# System_Ports.net
KiCad netlist of a schematic drawn in Altium Designer
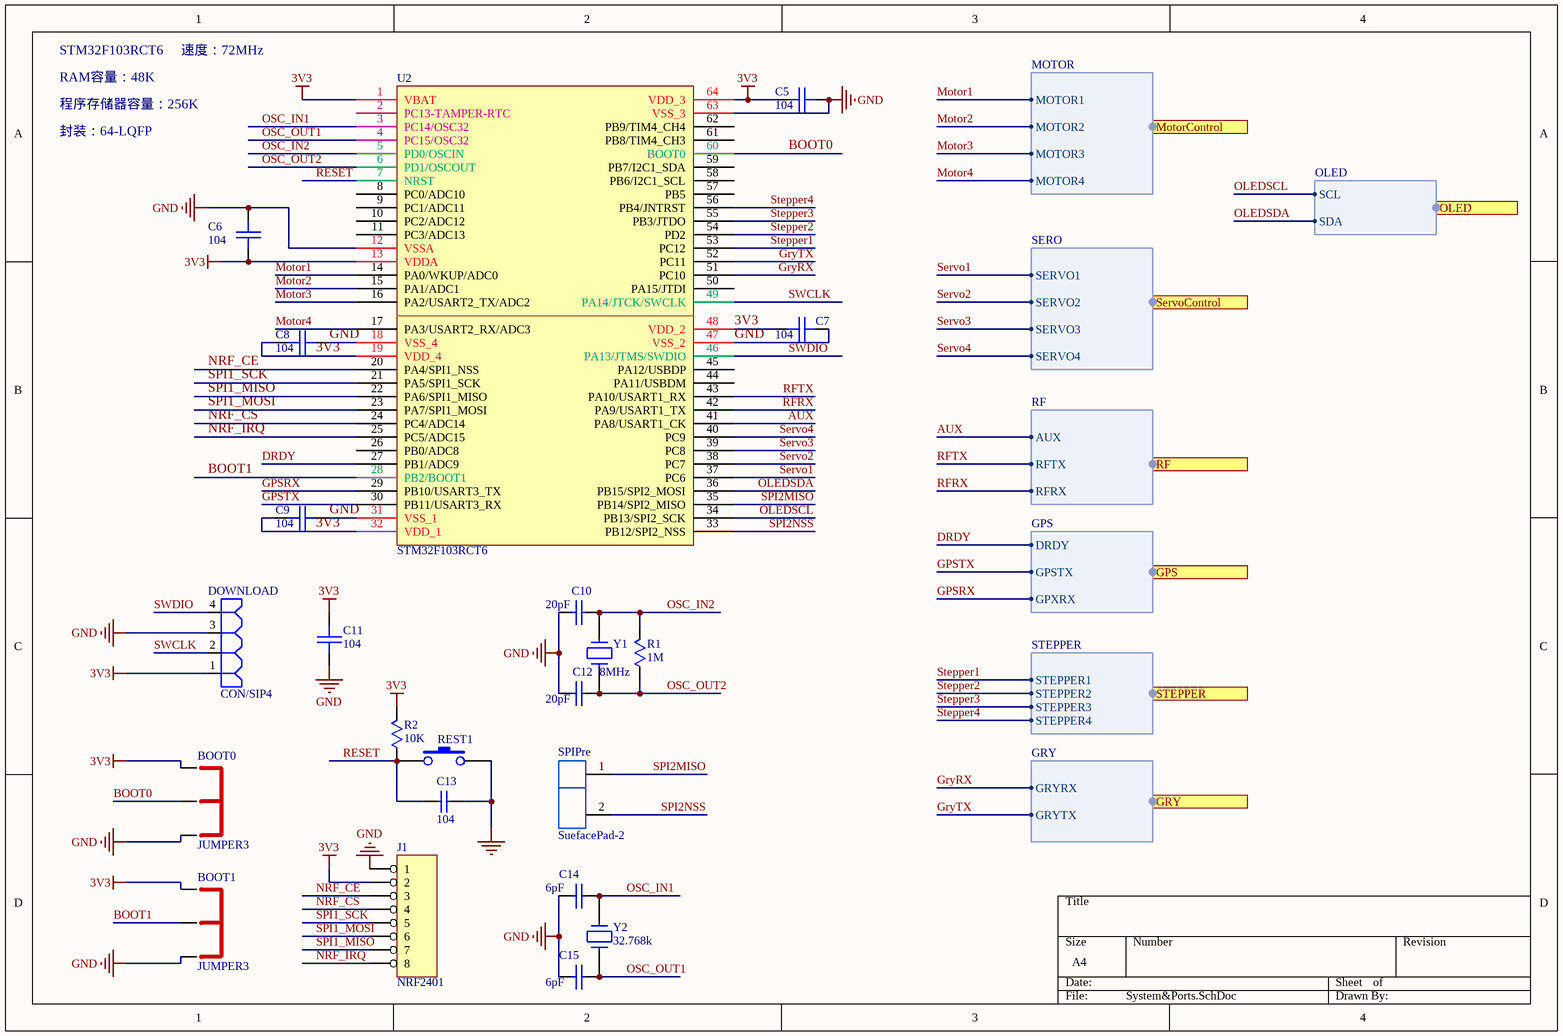
[diagram p0: System&Ports.SchDoc]

(export (version "E")
  (design (tool "Eeschema 10.0.6"))
  (components
    (comp (ref "BOOT0")
      (value "JUMPER3")
      (footprint "Jumper3")
      (description "Jumper")
      (libsource (lib "LQ_Integrated_Library") (part "JUMPER3"))
    )
    (comp (ref "BOOT1")
      (value "JUMPER3")
      (footprint "Jumper3")
      (description "Jumper")
      (libsource (lib "LQ_Integrated_Library") (part "JUMPER3"))
    )
    (comp (ref "C5") (value "104") (footprint "C0603") (libsource (lib "YT1_SCH_99SE") (part "CAP")))
    (comp (ref "C6") (value "104") (footprint "C0603") (libsource (lib "YT1_SCH_99SE") (part "CAP")))
    (comp (ref "C7") (value "104") (footprint "C0603") (libsource (lib "YT1_SCH_99SE") (part "CAP")))
    (comp (ref "C8") (value "104") (footprint "C0603") (libsource (lib "YT1_SCH_99SE") (part "CAP")))
    (comp (ref "C9") (value "104") (footprint "C0603") (libsource (lib "YT1_SCH_99SE") (part "CAP")))
    (comp (ref "C10")
      (value "20pF")
      (footprint "LC-0603_C")
      (description "CAP CHIP 20P 50V(+-5% C0G 0603)")
      (libsource (lib "Miscellaneous Devices") (part "CAP"))
    )
    (comp (ref "C11") (value "104") (footprint "C0603") (libsource (lib "YT1_SCH_99SE") (part "CAP")))
    (comp (ref "C12")
      (value "20pF")
      (footprint "LC-0603_C")
      (description "CAP CHIP 20P 50V(+-5% C0G 0603)")
      (libsource (lib "Miscellaneous Devices") (part "CAP"))
    )
    (comp (ref "C13")
      (value "104")
      (footprint "LC-0603_C")
      (description "GRM39 X7R102K50PT")
      (fields (field (name "PUBLISHER") "Altium Limited"))
      (libsource (lib "") (part "CAP_1"))
    )
    (comp (ref "C14")
      (value "6pF")
      (footprint "LC-0603_C")
      (description "CAP CHIP 20P 50V(+-5% C0G 0603)")
      (libsource (lib "Miscellaneous Devices") (part "CAP"))
    )
    (comp (ref "C15")
      (value "6pF")
      (footprint "LC-0603_C")
      (description "CAP CHIP 20P 50V(+-5% C0G 0603)")
      (libsource (lib "Miscellaneous Devices") (part "CAP"))
    )
    (comp (ref "DOWNLOAD")
      (value "CON/SIP4")
      (footprint "HDR1X4")
      (libsource (lib "LQ_Integrated_Library") (part "CON/SIP4"))
    )
    (comp (ref "J1")
      (value "NRF2401")
      (footprint "HDR2X4")
      (description "8 Pin Header")
      (libsource (lib "YT1_SCH_99SE") (part "HEADER 8"))
    )
    (comp (ref "R1") (value "1M") (footprint "LC-0603_R") (libsource (lib "YT1_SCH_99SE") (part "RES")))
    (comp (ref "R2") (value "10K") (footprint "R0603") (libsource (lib "YT1_SCH_99SE") (part "RES")))
    (comp (ref "REST1") (value "~") (footprint "KEY-K2") (libsource (lib "*") (part "SW-PB")))
    (comp (ref "SPIPre")
      (value "SuefacePad-2")
      (footprint "SurfacePad-2")
      (libsource (lib "FlyAndDive") (part "SurfacePad-2"))
    )
    (comp (ref "U2")
      (value "STM32F103RCT6")
      (footprint "LC-LQFP-64_10x10x05P")
      (libsource (lib "YT1_SCH_99SE") (part "STM32F103RBT6"))
    )
    (comp (ref "Y1")
      (value "8MHz")
      (footprint "XTAL-49/S_N")
      (description "Crystal 8MHz PLUG")
      (libsource (lib "*") (part "CRYSTAL"))
    )
    (comp (ref "Y2")
      (value "32.768k")
      (footprint "XTAL_2X6 卧式")
      (description "Crystal 8MHz PLUG")
      (libsource (lib "*") (part "CRYSTAL"))
    )
  )
  (nets
    (net (code "8") (name "/AUX") (class "Default")
      (node (ref "U2") (pin "41") (pinfunction "PA8/USART1_CK_41") (pintype "passive"))
    )
    (net (code "9") (name "/BOOT0") (class "Default")
      (node (ref "BOOT0") (pin "2") (pinfunction "2_2") (pintype "passive"))
      (node (ref "U2") (pin "60") (pinfunction "BOOT0_60") (pintype "passive"))
    )
    (net (code "10") (name "/BOOT1") (class "Default")
      (node (ref "BOOT1") (pin "2") (pinfunction "2_2") (pintype "passive"))
      (node (ref "U2") (pin "28") (pinfunction "PB2/BOOT1_28") (pintype "passive"))
    )
    (net (code "11") (name "/DRDY") (class "Default")
      (node (ref "U2") (pin "27") (pinfunction "PB1/ADC9_27") (pintype "passive"))
    )
    (net (code "12") (name "/GPSRX") (class "Default")
      (node (ref "U2") (pin "29") (pinfunction "PB10/USART3_TX_29") (pintype "passive"))
    )
    (net (code "13") (name "/GPSTX") (class "Default")
      (node (ref "U2") (pin "30") (pinfunction "PB11/USART3_RX_30") (pintype "passive"))
    )
    (net (code "14") (name "/GryRX") (class "Default")
      (node (ref "U2") (pin "51") (pinfunction "PC10_51") (pintype "passive"))
    )
    (net (code "15") (name "/GryTX") (class "Default")
      (node (ref "U2") (pin "52") (pinfunction "PC11_52") (pintype "passive"))
    )
    (net (code "16") (name "/Motor1") (class "Default")
      (node (ref "U2") (pin "14") (pinfunction "PA0/WKUP/ADC0_14") (pintype "passive"))
    )
    (net (code "17") (name "/Motor2") (class "Default")
      (node (ref "U2") (pin "15") (pinfunction "PA1/ADC1_15") (pintype "passive"))
    )
    (net (code "18") (name "/Motor3") (class "Default")
      (node (ref "U2") (pin "16") (pinfunction "PA2/USART2_TX/ADC2_16") (pintype "passive"))
    )
    (net (code "19") (name "/Motor4") (class "Default")
      (node (ref "U2") (pin "17") (pinfunction "PA3/USART2_RX/ADC3_17") (pintype "passive"))
    )
    (net (code "20") (name "/NRF_CE") (class "Default")
      (node (ref "J1") (pin "3") (pinfunction "3_3") (pintype "passive"))
      (node (ref "U2") (pin "20") (pinfunction "PA4/SPI1_NSS_20") (pintype "passive"))
    )
    (net (code "21") (name "/NRF_CS") (class "Default")
      (node (ref "J1") (pin "4") (pinfunction "4_4") (pintype "passive"))
      (node (ref "U2") (pin "24") (pinfunction "PC4/ADC14_24") (pintype "passive"))
    )
    (net (code "22") (name "/NRF_IRQ") (class "Default")
      (node (ref "J1") (pin "8") (pinfunction "8_8") (pintype "passive"))
      (node (ref "U2") (pin "25") (pinfunction "PC5/ADC15_25") (pintype "passive"))
    )
    (net (code "23") (name "/OLEDSCL") (class "Default")
      (node (ref "U2") (pin "34") (pinfunction "PB13/SPI2_SCK_34") (pintype "passive"))
    )
    (net (code "24") (name "/OLEDSDA") (class "Default")
      (node (ref "U2") (pin "36") (pinfunction "PB15/SPI2_MOSI_36") (pintype "passive"))
    )
    (net (code "25") (name "/OSC_IN1") (class "Default")
      (node (ref "C14") (pin "2") (pinfunction "2_2") (pintype "passive"))
      (node (ref "U2") (pin "3") (pinfunction "PC14/OSC32_3") (pintype "passive"))
      (node (ref "Y2") (pin "2") (pinfunction "2_2") (pintype "passive"))
    )
    (net (code "26") (name "/OSC_IN2") (class "Default")
      (node (ref "C10") (pin "2") (pinfunction "2_2") (pintype "passive"))
      (node (ref "R1") (pin "2") (pinfunction "2_2") (pintype "passive"))
      (node (ref "U2") (pin "5") (pinfunction "PD0/OSCIN_5") (pintype "passive"))
      (node (ref "Y1") (pin "1") (pinfunction "1_1") (pintype "passive"))
    )
    (net (code "27") (name "/OSC_OUT1") (class "Default")
      (node (ref "C15") (pin "2") (pinfunction "2_2") (pintype "passive"))
      (node (ref "U2") (pin "4") (pinfunction "PC15/OSC32_4") (pintype "passive"))
      (node (ref "Y2") (pin "1") (pinfunction "1_1") (pintype "passive"))
    )
    (net (code "28") (name "/OSC_OUT2") (class "Default")
      (node (ref "C12") (pin "2") (pinfunction "2_2") (pintype "passive"))
      (node (ref "R1") (pin "1") (pinfunction "1_1") (pintype "passive"))
      (node (ref "U2") (pin "6") (pinfunction "PD1/OSCOUT_6") (pintype "passive"))
      (node (ref "Y1") (pin "2") (pinfunction "2_2") (pintype "passive"))
    )
    (net (code "29") (name "/RESET") (class "Default")
      (node (ref "C13") (pin "2") (pinfunction "2_2") (pintype "passive"))
      (node (ref "R2") (pin "1") (pinfunction "1_1") (pintype "passive"))
      (node (ref "REST1") (pin "1") (pinfunction "1_1") (pintype "passive"))
      (node (ref "U2") (pin "7") (pinfunction "NRST_7") (pintype "passive"))
    )
    (net (code "30") (name "/RFRX") (class "Default")
      (node (ref "U2") (pin "42") (pinfunction "PA9/USART1_TX_42") (pintype "passive"))
    )
    (net (code "31") (name "/RFTX") (class "Default")
      (node (ref "U2") (pin "43") (pinfunction "PA10/USART1_RX_43") (pintype "passive"))
    )
    (net (code "32") (name "/SPI1_MISO") (class "Default")
      (node (ref "J1") (pin "7") (pinfunction "7_7") (pintype "passive"))
      (node (ref "U2") (pin "22") (pinfunction "PA6/SPI1_MISO_22") (pintype "passive"))
    )
    (net (code "33") (name "/SPI1_MOSI") (class "Default")
      (node (ref "J1") (pin "6") (pinfunction "6_6") (pintype "passive"))
      (node (ref "U2") (pin "23") (pinfunction "PA7/SPI1_MOSI_23") (pintype "passive"))
    )
    (net (code "34") (name "/SPI1_SCK") (class "Default")
      (node (ref "J1") (pin "5") (pinfunction "5_5") (pintype "passive"))
      (node (ref "U2") (pin "21") (pinfunction "PA5/SPI1_SCK_21") (pintype "passive"))
    )
    (net (code "35") (name "/SPI2MISO") (class "Default")
      (node (ref "SPIPre") (pin "1") (pinfunction "1_1") (pintype "passive"))
      (node (ref "U2") (pin "35") (pinfunction "PB14/SPI2_MISO_35") (pintype "passive"))
    )
    (net (code "36") (name "/SPI2NSS") (class "Default")
      (node (ref "SPIPre") (pin "2") (pinfunction "2_2") (pintype "passive"))
      (node (ref "U2") (pin "33") (pinfunction "PB12/SPI2_NSS_33") (pintype "passive"))
    )
    (net (code "37") (name "/SWCLK") (class "Default")
      (node (ref "DOWNLOAD") (pin "2") (pintype "passive"))
      (node (ref "U2") (pin "49") (pinfunction "PA14/JTCK/SWCLK_49") (pintype "passive"))
    )
    (net (code "38") (name "/SWDIO") (class "Default")
      (node (ref "DOWNLOAD") (pin "4") (pintype "passive"))
      (node (ref "U2") (pin "46") (pinfunction "PA13/JTMS/SWDIO_46") (pintype "passive"))
    )
    (net (code "39") (name "/Servo1") (class "Default")
      (node (ref "U2") (pin "37") (pinfunction "PC6_37") (pintype "passive"))
    )
    (net (code "40") (name "/Servo2") (class "Default")
      (node (ref "U2") (pin "38") (pinfunction "PC7_38") (pintype "passive"))
    )
    (net (code "41") (name "/Servo3") (class "Default")
      (node (ref "U2") (pin "39") (pinfunction "PC8_39") (pintype "passive"))
    )
    (net (code "42") (name "/Servo4") (class "Default")
      (node (ref "U2") (pin "40") (pinfunction "PC9_40") (pintype "passive"))
    )
    (net (code "43") (name "/Stepper1") (class "Default")
      (node (ref "U2") (pin "53") (pinfunction "PC12_53") (pintype "passive"))
    )
    (net (code "44") (name "/Stepper2") (class "Default")
      (node (ref "U2") (pin "54") (pinfunction "PD2_54") (pintype "passive"))
    )
    (net (code "45") (name "/Stepper3") (class "Default")
      (node (ref "U2") (pin "55") (pinfunction "PB3/JTDO_55") (pintype "passive"))
    )
    (net (code "46") (name "/Stepper4") (class "Default")
      (node (ref "U2") (pin "56") (pinfunction "PB4/JNTRST_56") (pintype "passive"))
    )
    (net (code "54") (name "3V3") (class "Default")
      (node (ref "BOOT0") (pin "1") (pinfunction "1_1") (pintype "passive"))
      (node (ref "BOOT1") (pin "1") (pinfunction "1_1") (pintype "passive"))
      (node (ref "C11") (pin "1") (pinfunction "1_1") (pintype "passive"))
      (node (ref "C5") (pin "1") (pinfunction "1_1") (pintype "passive"))
      (node (ref "C6") (pin "2") (pinfunction "2_2") (pintype "passive"))
      (node (ref "C7") (pin "1") (pinfunction "1_1") (pintype "passive"))
      (node (ref "C8") (pin "1") (pinfunction "1_1") (pintype "passive"))
      (node (ref "C9") (pin "1") (pinfunction "1_1") (pintype "passive"))
      (node (ref "DOWNLOAD") (pin "1") (pintype "passive"))
      (node (ref "J1") (pin "2") (pinfunction "2_2") (pintype "passive"))
      (node (ref "R2") (pin "2") (pinfunction "2_2") (pintype "passive"))
      (node (ref "U2") (pin "1") (pinfunction "VBAT_1") (pintype "passive"))
      (node (ref "U2") (pin "13") (pinfunction "VDDA_13") (pintype "passive"))
      (node (ref "U2") (pin "19") (pinfunction "VDD_4_19") (pintype "passive"))
      (node (ref "U2") (pin "32") (pinfunction "VDD_1_32") (pintype "passive"))
      (node (ref "U2") (pin "48") (pinfunction "VDD_2_48") (pintype "passive"))
      (node (ref "U2") (pin "64") (pinfunction "VDD_3_64") (pintype "passive"))
    )
    (net (code "55") (name "GND") (class "Default")
      (node (ref "BOOT0") (pin "3") (pinfunction "3_3") (pintype "passive"))
      (node (ref "BOOT1") (pin "3") (pinfunction "3_3") (pintype "passive"))
      (node (ref "C10") (pin "1") (pinfunction "1_1") (pintype "passive"))
      (node (ref "C11") (pin "2") (pinfunction "2_2") (pintype "passive"))
      (node (ref "C12") (pin "1") (pinfunction "1_1") (pintype "passive"))
      (node (ref "C13") (pin "1") (pinfunction "1_1") (pintype "passive"))
      (node (ref "C14") (pin "1") (pinfunction "1_1") (pintype "passive"))
      (node (ref "C15") (pin "1") (pinfunction "1_1") (pintype "passive"))
      (node (ref "C5") (pin "2") (pinfunction "2_2") (pintype "passive"))
      (node (ref "C6") (pin "1") (pinfunction "1_1") (pintype "passive"))
      (node (ref "C7") (pin "2") (pinfunction "2_2") (pintype "passive"))
      (node (ref "C8") (pin "2") (pinfunction "2_2") (pintype "passive"))
      (node (ref "C9") (pin "2") (pinfunction "2_2") (pintype "passive"))
      (node (ref "DOWNLOAD") (pin "3") (pintype "passive"))
      (node (ref "J1") (pin "1") (pinfunction "1_1") (pintype "passive"))
      (node (ref "REST1") (pin "2") (pinfunction "2_2") (pintype "passive"))
      (node (ref "U2") (pin "12") (pinfunction "VSSA_12") (pintype "passive"))
      (node (ref "U2") (pin "18") (pinfunction "VSS_4_18") (pintype "passive"))
      (node (ref "U2") (pin "31") (pinfunction "VSS_1_31") (pintype "passive"))
      (node (ref "U2") (pin "47") (pinfunction "VSS_2_47") (pintype "passive"))
      (node (ref "U2") (pin "63") (pinfunction "VSS_3_63") (pintype "passive"))
    )
    (net (code "56") (name "unconnected-(U2-PA11{slash}USBDM-Pad44)") (class "Default")
      (node (ref "U2") (pin "44") (pinfunction "PA11/USBDM_44") (pintype "passive"))
    )
    (net (code "57") (name "unconnected-(U2-PA12{slash}USBDP-Pad45)") (class "Default")
      (node (ref "U2") (pin "45") (pinfunction "PA12/USBDP_45") (pintype "passive"))
    )
    (net (code "58") (name "unconnected-(U2-PA15{slash}JTDI-Pad50)") (class "Default")
      (node (ref "U2") (pin "50") (pinfunction "PA15/JTDI_50") (pintype "passive"))
    )
    (net (code "59") (name "unconnected-(U2-PB0{slash}ADC8-Pad26)") (class "Default")
      (node (ref "U2") (pin "26") (pinfunction "PB0/ADC8_26") (pintype "passive"))
    )
    (net (code "60") (name "unconnected-(U2-PB5-Pad57)") (class "Default")
      (node (ref "U2") (pin "57") (pinfunction "PB5_57") (pintype "passive"))
    )
    (net (code "61") (name "unconnected-(U2-PB6{slash}I2C1_SCL-Pad58)") (class "Default")
      (node (ref "U2") (pin "58") (pinfunction "PB6/I2C1_SCL_58") (pintype "passive"))
    )
    (net (code "62") (name "unconnected-(U2-PB7{slash}I2C1_SDA-Pad59)") (class "Default")
      (node (ref "U2") (pin "59") (pinfunction "PB7/I2C1_SDA_59") (pintype "passive"))
    )
    (net (code "63") (name "unconnected-(U2-PB8{slash}TIM4_CH3-Pad61)") (class "Default")
      (node (ref "U2") (pin "61") (pinfunction "PB8/TIM4_CH3_61") (pintype "passive"))
    )
    (net (code "64") (name "unconnected-(U2-PB9{slash}TIM4_CH4-Pad62)") (class "Default")
      (node (ref "U2") (pin "62") (pinfunction "PB9/TIM4_CH4_62") (pintype "passive"))
    )
    (net (code "65") (name "unconnected-(U2-PC0{slash}ADC10-Pad8)") (class "Default")
      (node (ref "U2") (pin "8") (pinfunction "PC0/ADC10_8") (pintype "passive"))
    )
    (net (code "66") (name "unconnected-(U2-PC1{slash}ADC11-Pad9)") (class "Default")
      (node (ref "U2") (pin "9") (pinfunction "PC1/ADC11_9") (pintype "passive"))
    )
    (net (code "67") (name "unconnected-(U2-PC2{slash}ADC12-Pad10)") (class "Default")
      (node (ref "U2") (pin "10") (pinfunction "PC2/ADC12_10") (pintype "passive"))
    )
    (net (code "68") (name "unconnected-(U2-PC3{slash}ADC13-Pad11)") (class "Default")
      (node (ref "U2") (pin "11") (pinfunction "PC3/ADC13_11") (pintype "passive"))
    )
    (net (code "69") (name "unconnected-(U2-PC13-TAMPER-RTC-Pad2)") (class "Default")
      (node (ref "U2") (pin "2") (pinfunction "PC13-TAMPER-RTC_2") (pintype "passive"))
    )
  )
)
